# DSO_CPLD.net
KiCad netlist of a schematic drawn in Altium Designer
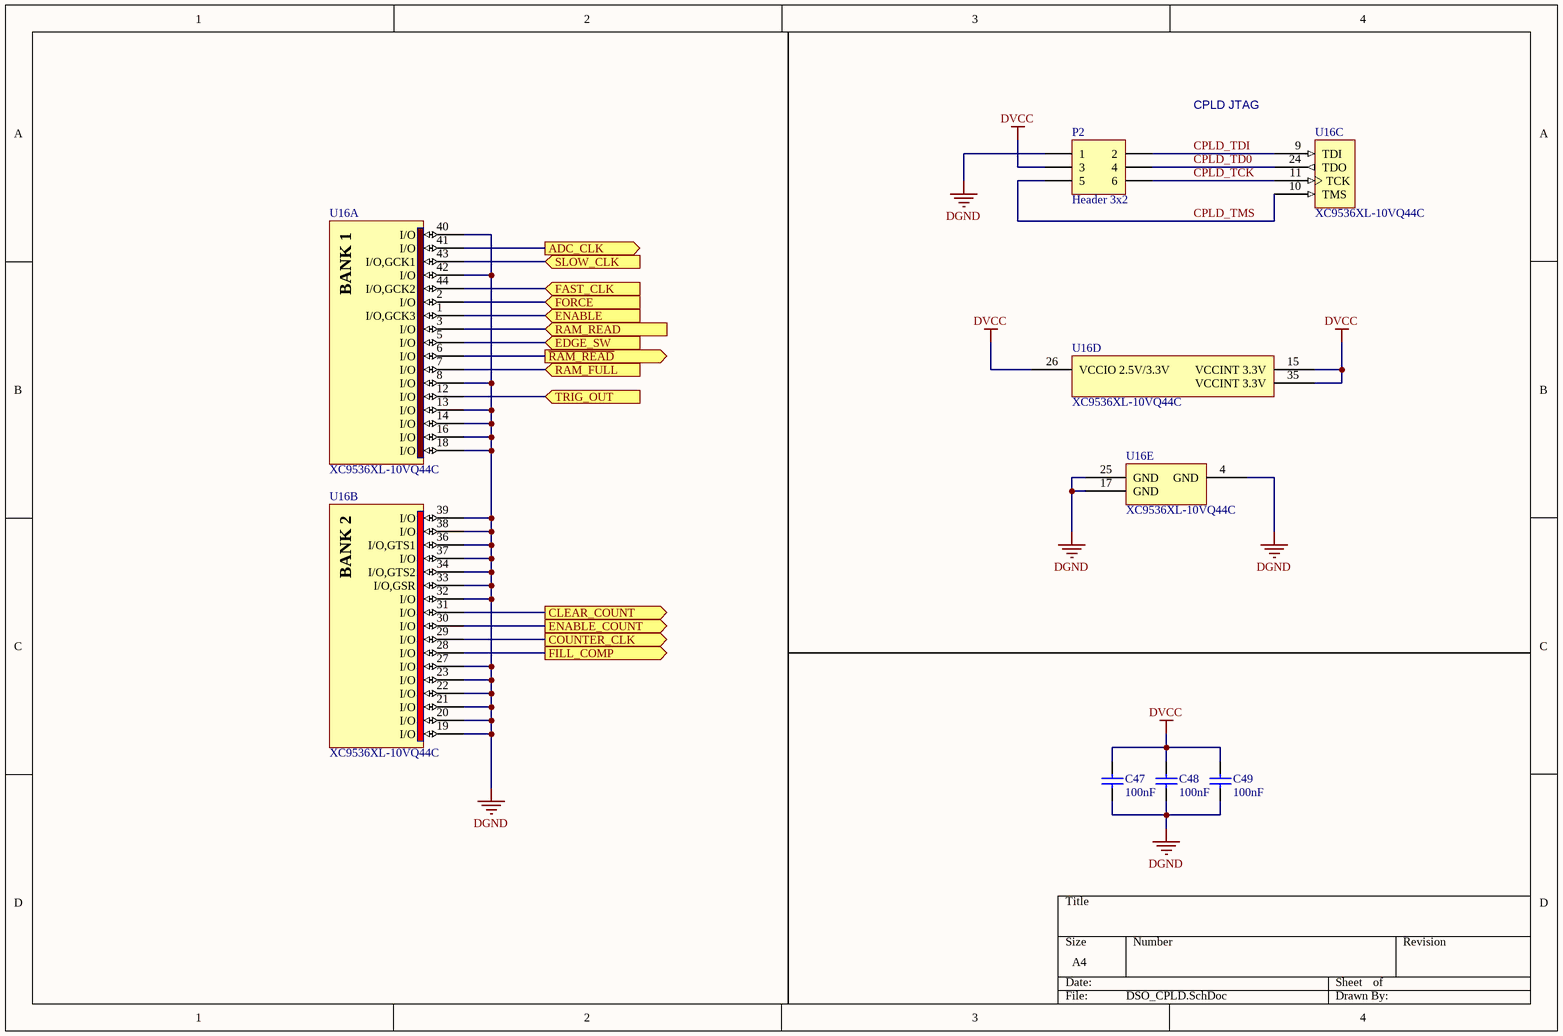
[diagram p0: DSO_CPLD.SchDoc]

(export (version "E")
  (design (tool "Eeschema 10.0.6"))
  (components
    (comp (ref "C47")
      (value "100nF")
      (footprint "0805C")
      (description "Capacitor")
      (fields (field (name "REVIEWED BY") "RM - 2018/08/05"))
      (libsource (lib "DSO") (part "C"))
    )
    (comp (ref "C48")
      (value "100nF")
      (footprint "0805C")
      (description "Capacitor")
      (fields (field (name "REVIEWED BY") "RM - 2018/08/05"))
      (libsource (lib "DSO") (part "C"))
    )
    (comp (ref "C49")
      (value "100nF")
      (footprint "0805C")
      (description "Capacitor")
      (fields (field (name "REVIEWED BY") "RM - 2018/08/05"))
      (libsource (lib "DSO") (part "C"))
    )
    (comp (ref "P2")
      (value "Header 3x2")
      (footprint "HDR3x2")
      (description "Header, 5-Pin")
      (fields (field (name "REVIEWED BY") "RM - 2018/08/05"))
      (libsource (lib "DSO") (part "Header 3x2"))
    )
    (comp (ref "U16")
      (value "XC9536XL-10VQ44C")
      (footprint "VQ44_L")
      (fields (field (name "REVIEWED BY") "RM - 2018/08/05"))
      (libsource (lib "DSO") (part "XC9536XL-10VQG44C"))
    )
  )
  (nets
    (net (code "1") (name "/ADC_CLK") (class "Default")
      (node (ref "U16") (pin "41") (pinfunction "I/O_41") (pintype "bidirectional"))
    )
    (net (code "2") (name "/CLEAR_COUNT") (class "Default")
      (node (ref "U16") (pin "31") (pinfunction "I/O_31") (pintype "bidirectional"))
    )
    (net (code "3") (name "/COUNTER_CLK") (class "Default")
      (node (ref "U16") (pin "29") (pinfunction "I/O_29") (pintype "bidirectional"))
    )
    (net (code "4") (name "/CPLD_TCK") (class "Default")
      (node (ref "P2") (pin "6") (pinfunction "6_6") (pintype "passive"))
      (node (ref "U16") (pin "11") (pinfunction "TCK_11") (pintype "input"))
    )
    (net (code "5") (name "/CPLD_TD0") (class "Default")
      (node (ref "P2") (pin "4") (pinfunction "4_4") (pintype "passive"))
      (node (ref "U16") (pin "24") (pinfunction "TDO_24") (pintype "output"))
    )
    (net (code "6") (name "/CPLD_TDI") (class "Default")
      (node (ref "P2") (pin "2") (pinfunction "2_2") (pintype "passive"))
      (node (ref "U16") (pin "9") (pinfunction "TDI_9") (pintype "input"))
    )
    (net (code "7") (name "/CPLD_TMS") (class "Default")
      (node (ref "P2") (pin "5") (pinfunction "5_5") (pintype "passive"))
      (node (ref "U16") (pin "10") (pinfunction "TMS_10") (pintype "input"))
    )
    (net (code "8") (name "/EDGE_SW") (class "Default")
      (node (ref "U16") (pin "5") (pinfunction "I/O_5") (pintype "bidirectional"))
    )
    (net (code "9") (name "/ENABLE") (class "Default")
      (node (ref "U16") (pin "1") (pinfunction "I/O,GCK3_1") (pintype "bidirectional"))
    )
    (net (code "10") (name "/ENABLE_COUNT") (class "Default")
      (node (ref "U16") (pin "30") (pinfunction "I/O_30") (pintype "bidirectional"))
    )
    (net (code "11") (name "/FAST_CLK") (class "Default")
      (node (ref "U16") (pin "44") (pinfunction "I/O,GCK2_44") (pintype "bidirectional"))
    )
    (net (code "12") (name "/FILL_COMP") (class "Default")
      (node (ref "U16") (pin "28") (pinfunction "I/O_28") (pintype "bidirectional"))
    )
    (net (code "13") (name "/FORCE") (class "Default")
      (node (ref "U16") (pin "2") (pinfunction "I/O_2") (pintype "bidirectional"))
    )
    (net (code "14") (name "/RAM_FULL") (class "Default")
      (node (ref "U16") (pin "7") (pinfunction "I/O_7") (pintype "bidirectional"))
    )
    (net (code "15") (name "/RAM_READ") (class "Default")
      (node (ref "U16") (pin "3") (pinfunction "I/O_3") (pintype "bidirectional"))
    )
    (net (code "16") (name "/SLOW_CLK") (class "Default")
      (node (ref "U16") (pin "43") (pinfunction "I/O,GCK1_43") (pintype "bidirectional"))
    )
    (net (code "17") (name "/TRIG_OUT") (class "Default")
      (node (ref "U16") (pin "12") (pinfunction "I/O_12") (pintype "bidirectional"))
    )
    (net (code "18") (name "/~{RAM_READ}") (class "Default")
      (node (ref "U16") (pin "6") (pinfunction "I/O_6") (pintype "bidirectional"))
    )
    (net (code "19") (name "DGND") (class "Default")
      (node (ref "C47") (pin "2") (pinfunction "2_2") (pintype "passive"))
      (node (ref "C48") (pin "2") (pinfunction "2_2") (pintype "passive"))
      (node (ref "C49") (pin "2") (pinfunction "2_2") (pintype "passive"))
      (node (ref "P2") (pin "1") (pinfunction "1_1") (pintype "passive"))
      (node (ref "U16") (pin "13") (pinfunction "I/O_13") (pintype "bidirectional"))
      (node (ref "U16") (pin "14") (pinfunction "I/O_14") (pintype "bidirectional"))
      (node (ref "U16") (pin "16") (pinfunction "I/O_16") (pintype "bidirectional"))
      (node (ref "U16") (pin "17") (pinfunction "GND_17") (pintype "power_in"))
      (node (ref "U16") (pin "18") (pinfunction "I/O_18") (pintype "bidirectional"))
      (node (ref "U16") (pin "19") (pinfunction "I/O_19") (pintype "bidirectional"))
      (node (ref "U16") (pin "20") (pinfunction "I/O_20") (pintype "bidirectional"))
      (node (ref "U16") (pin "21") (pinfunction "I/O_21") (pintype "bidirectional"))
      (node (ref "U16") (pin "22") (pinfunction "I/O_22") (pintype "bidirectional"))
      (node (ref "U16") (pin "23") (pinfunction "I/O_23") (pintype "bidirectional"))
      (node (ref "U16") (pin "25") (pinfunction "GND_25") (pintype "power_in"))
      (node (ref "U16") (pin "27") (pinfunction "I/O_27") (pintype "bidirectional"))
      (node (ref "U16") (pin "32") (pinfunction "I/O_32") (pintype "bidirectional"))
      (node (ref "U16") (pin "33") (pinfunction "I/O,GSR_33") (pintype "bidirectional"))
      (node (ref "U16") (pin "34") (pinfunction "I/O,GTS2_34") (pintype "bidirectional"))
      (node (ref "U16") (pin "36") (pinfunction "I/O,GTS1_36") (pintype "bidirectional"))
      (node (ref "U16") (pin "37") (pinfunction "I/O_37") (pintype "bidirectional"))
      (node (ref "U16") (pin "38") (pinfunction "I/O_38") (pintype "bidirectional"))
      (node (ref "U16") (pin "39") (pinfunction "I/O_39") (pintype "bidirectional"))
      (node (ref "U16") (pin "4") (pinfunction "GND_4") (pintype "power_in"))
      (node (ref "U16") (pin "40") (pinfunction "I/O_40") (pintype "bidirectional"))
      (node (ref "U16") (pin "42") (pinfunction "I/O_42") (pintype "bidirectional"))
      (node (ref "U16") (pin "8") (pinfunction "I/O_8") (pintype "bidirectional"))
    )
    (net (code "20") (name "DVCC") (class "Default")
      (node (ref "C47") (pin "1") (pinfunction "1_1") (pintype "passive"))
      (node (ref "C48") (pin "1") (pinfunction "1_1") (pintype "passive"))
      (node (ref "C49") (pin "1") (pinfunction "1_1") (pintype "passive"))
      (node (ref "P2") (pin "3") (pinfunction "3_3") (pintype "passive"))
      (node (ref "U16") (pin "15") (pinfunction "VCCINT_3.3V_15") (pintype "power_in"))
      (node (ref "U16") (pin "26") (pinfunction "VCCIO_2.5V/3.3V_26") (pintype "power_in"))
      (node (ref "U16") (pin "35") (pinfunction "VCCINT_3.3V_35") (pintype "power_in"))
    )
  )
)
